# thread_dongle.net
KiCad netlist of a schematic drawn in EAGLE
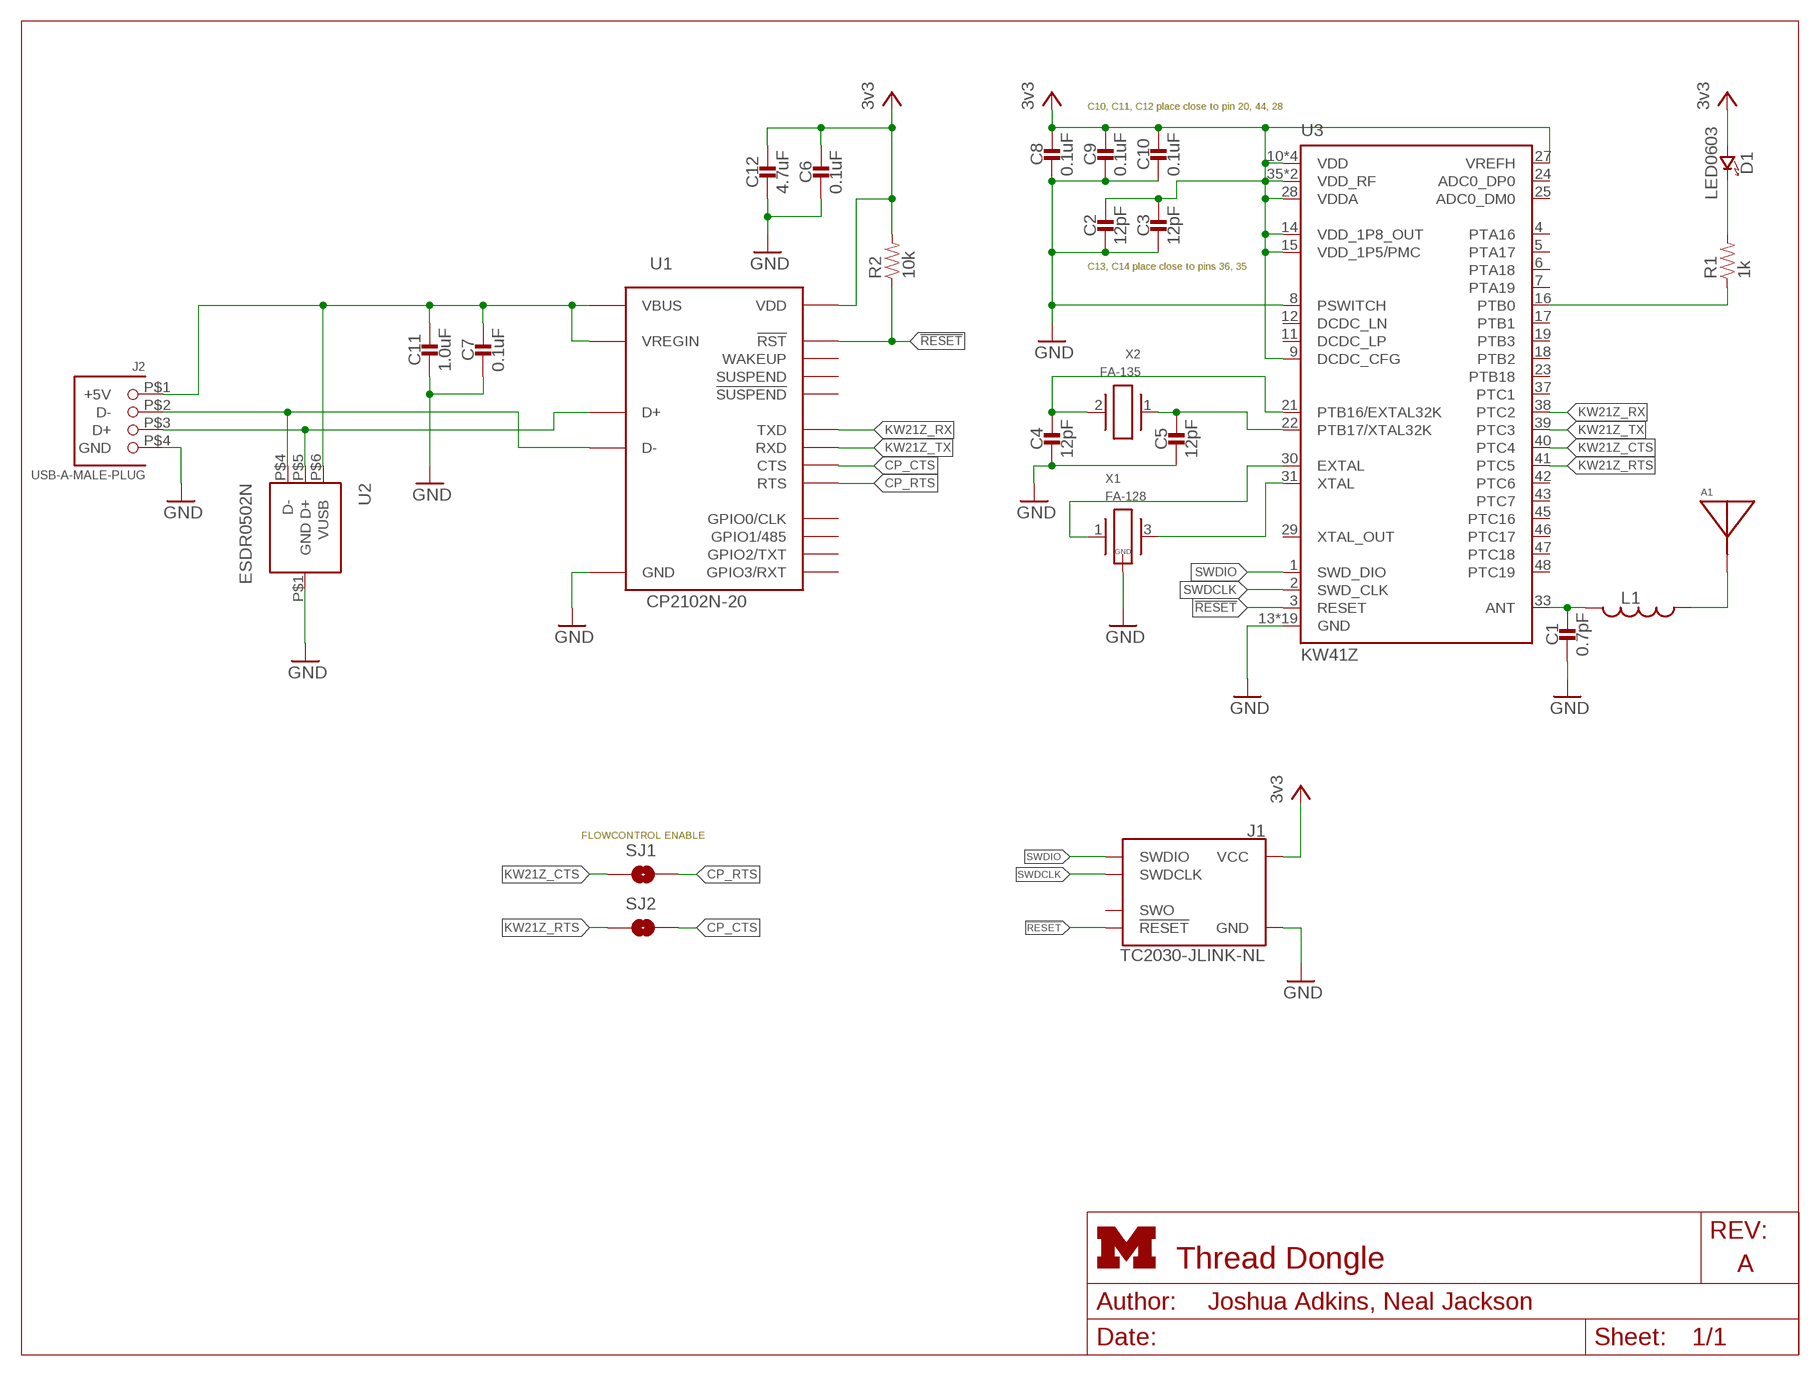
[diagram p0: schematic, sheet 1]

(export (version "E")
  (design (tool "Eeschema 10.0.6"))
  (components
    (comp (ref "A1")
      (value "AH212M")
      (footprint "eagle-import:AH212M")
      (fields (field (name "MPN") "AH212M245001-T"))
      (libsource (lib "eagle-import") (part "AH212M"))
    )
    (comp (ref "C1")
      (value "0.7pF")
      (footprint "eagle-import:0402_CAP")
      (fields (field (name "MPN") "GRM1555C1HR70BA01D"))
      (libsource (lib "eagle-import") (part "CAPACITOR0402_CAP"))
    )
    (comp (ref "C2")
      (value "12pF")
      (footprint "eagle-import:0402_CAP")
      (fields (field (name "MPN") "GRM1555C1H120JA01D"))
      (libsource (lib "eagle-import") (part "CAPACITOR0402_CAP"))
    )
    (comp (ref "C3")
      (value "12pF")
      (footprint "eagle-import:0402_CAP")
      (fields (field (name "MPN") "GRM1555C1H120JA01D"))
      (libsource (lib "eagle-import") (part "CAPACITOR0402_CAP"))
    )
    (comp (ref "C4")
      (value "12pF")
      (footprint "eagle-import:0402_CAP")
      (fields (field (name "MPN") "GRM1555C1H120JA01D"))
      (libsource (lib "eagle-import") (part "CAPACITOR0402_CAP"))
    )
    (comp (ref "C5")
      (value "12pF")
      (footprint "eagle-import:0402_CAP")
      (fields (field (name "MPN") "GRM1555C1H120JA01D"))
      (libsource (lib "eagle-import") (part "CAPACITOR0402_CAP"))
    )
    (comp (ref "C6")
      (value "0.1uF")
      (footprint "eagle-import:0402_CAP")
      (fields (field (name "MPN") "LMK105BJ104KV-F"))
      (libsource (lib "eagle-import") (part "CAPACITOR0402_CAP"))
    )
    (comp (ref "C7")
      (value "0.1uF")
      (footprint "eagle-import:0402_CAP")
      (fields (field (name "MPN") "LMK105BJ104KV-F"))
      (libsource (lib "eagle-import") (part "CAPACITOR0402_CAP"))
    )
    (comp (ref "C8")
      (value "0.1uF")
      (footprint "eagle-import:0402_CAP")
      (fields (field (name "MPN") "LMK105BJ104KV-F"))
      (libsource (lib "eagle-import") (part "CAPACITOR0402_CAP"))
    )
    (comp (ref "C9")
      (value "0.1uF")
      (footprint "eagle-import:0402_CAP")
      (fields (field (name "MPN") "LMK105BJ104KV-F"))
      (libsource (lib "eagle-import") (part "CAPACITOR0402_CAP"))
    )
    (comp (ref "C10")
      (value "0.1uF")
      (footprint "eagle-import:0402_CAP")
      (fields (field (name "MPN") "LMK105BJ104KV-F"))
      (libsource (lib "eagle-import") (part "CAPACITOR0402_CAP"))
    )
    (comp (ref "C11")
      (value "1.0uF")
      (footprint "eagle-import:0402_CAP")
      (fields (field (name "MPN") "GRM155R61E105MA12D"))
      (libsource (lib "eagle-import") (part "CAPACITOR0402_CAP"))
    )
    (comp (ref "C12")
      (value "4.7uF")
      (footprint "eagle-import:0402_CAP")
      (fields (field (name "MPN") "GRM155R60J475ME47D"))
      (libsource (lib "eagle-import") (part "CAPACITOR0402_CAP"))
    )
    (comp (ref "D1")
      (value "LED0603")
      (footprint "eagle-import:LED-0603")
      (fields (field (name "MPN") "LTST-C194TBKT"))
      (libsource (lib "eagle-import") (part "LED0603"))
    )
    (comp (ref "J1")
      (value "TC2030-JLINK-NL")
      (footprint "eagle-import:TC2030-IDC-NL")
      (libsource (lib "eagle-import") (part "TC2030-JLINK-NL"))
    )
    (comp (ref "J2")
      (value "USB-A-MALE-PLUG")
      (footprint "eagle-import:USB_A_MALE_PLUG_CUI_UP2-AH")
      (fields (field (name "MANUFACTURER") "CUI") (field (name "MPN") "UP2-AH-1-TH"))
      (libsource (lib "eagle-import") (part "USB-A-MALE-PLUG"))
    )
    (comp (ref "L1")
      (value "INDUCTOR0402")
      (footprint "eagle-import:0402_CAP")
      (fields (field (name "MPN") "LQG15HS5N1S02D"))
      (libsource (lib "eagle-import") (part "INDUCTOR0402"))
    )
    (comp (ref "R1")
      (value "1k")
      (footprint "eagle-import:0402_RES")
      (fields (field (name "MPN") "RC0402JR-071KL"))
      (libsource (lib "eagle-import") (part "RESISTOR0402_RES"))
    )
    (comp (ref "R2")
      (value "10k")
      (footprint "eagle-import:0402_RES")
      (fields (field (name "MPN") "RC0402JR-0710KL"))
      (libsource (lib "eagle-import") (part "RESISTOR0402_RES"))
    )
    (comp (ref "SJ1")
      (value "SOLDERJUMPERNC")
      (footprint "eagle-import:SJ_2S_SMALL")
      (libsource (lib "eagle-import") (part "SOLDERJUMPERNC"))
    )
    (comp (ref "SJ2")
      (value "SOLDERJUMPERNC")
      (footprint "eagle-import:SJ_2S_SMALL")
      (libsource (lib "eagle-import") (part "SOLDERJUMPERNC"))
    )
    (comp (ref "U1")
      (value "CP2102N-20")
      (footprint "eagle-import:QFN-20-3MM")
      (fields (field (name "MANUFACTURER") "SiLabs") (field (name "MPN") "CP2102N-A01-GQFN20"))
      (libsource (lib "eagle-import") (part "CP2102N-20"))
    )
    (comp (ref "U2")
      (value "ESDR0502N")
      (footprint "eagle-import:UDFN-6")
      (fields (field (name "MPN") "ESDR0502NMUTBG"))
      (libsource (lib "eagle-import") (part "ESDR0502N"))
    )
    (comp (ref "U3")
      (value "KW41Z")
      (footprint "eagle-import:LAMINATE-QFN-48-7MM")
      (fields (field (name "MPN") "MKW41Z512VHT4"))
      (libsource (lib "eagle-import") (part "KW41Z"))
    )
    (comp (ref "X1")
      (value "FA-128")
      (footprint "eagle-import:FA-128")
      (fields (field (name "MPN") "FA-128 32.0000MF20X-K5"))
      (libsource (lib "eagle-import") (part "FA-128"))
    )
    (comp (ref "X2")
      (value "FA-135")
      (footprint "eagle-import:FC-135")
      (fields (field (name "MPN") "FC-135 32.7680KA-AG3"))
      (libsource (lib "eagle-import") (part "FA-135"))
    )
  )
  (nets
    (net (code "1") (name "/~{RESET}") (class "Default")
      (node (ref "J1") (pin "3") (pinfunction "~{RESET}_3") (pintype "bidirectional"))
      (node (ref "R2") (pin "1") (pinfunction "1_1") (pintype "passive"))
      (node (ref "U1") (pin "9") (pinfunction "~{RST}_9") (pintype "bidirectional"))
      (node (ref "U3") (pin "3") (pinfunction "RESET_3") (pintype "bidirectional"))
    )
    (net (code "2") (name "3v3") (class "Default")
      (node (ref "C10") (pin "1") (pinfunction "1_1") (pintype "bidirectional"))
      (node (ref "C12") (pin "1") (pinfunction "1_1") (pintype "bidirectional"))
      (node (ref "C2") (pin "1") (pinfunction "1_1") (pintype "bidirectional"))
      (node (ref "C3") (pin "1") (pinfunction "1_1") (pintype "bidirectional"))
      (node (ref "C6") (pin "1") (pinfunction "1_1") (pintype "bidirectional"))
      (node (ref "C8") (pin "1") (pinfunction "1_1") (pintype "bidirectional"))
      (node (ref "C9") (pin "1") (pinfunction "1_1") (pintype "bidirectional"))
      (node (ref "D1") (pin "A") (pinfunction "ANODE_A") (pintype "bidirectional"))
      (node (ref "J1") (pin "1") (pinfunction "VCC_1") (pintype "bidirectional"))
      (node (ref "R2") (pin "2") (pinfunction "2_2") (pintype "passive"))
      (node (ref "U1") (pin "6") (pinfunction "VDD_6") (pintype "bidirectional"))
      (node (ref "U3") (pin "10") (pinfunction "VDD_10") (pintype "bidirectional"))
      (node (ref "U3") (pin "14") (pinfunction "VDD_1P8_OUT_14") (pintype "bidirectional"))
      (node (ref "U3") (pin "15") (pinfunction "VDD_1P5/PMC_15") (pintype "bidirectional"))
      (node (ref "U3") (pin "20") (pinfunction "VDD_20") (pintype "bidirectional"))
      (node (ref "U3") (pin "27") (pinfunction "VREFH_27") (pintype "bidirectional"))
      (node (ref "U3") (pin "28") (pinfunction "VDDA_28") (pintype "bidirectional"))
      (node (ref "U3") (pin "32") (pinfunction "VDD_32") (pintype "bidirectional"))
      (node (ref "U3") (pin "35") (pinfunction "VDD_RF_35") (pintype "bidirectional"))
      (node (ref "U3") (pin "36") (pinfunction "VDD_RF_36") (pintype "bidirectional"))
      (node (ref "U3") (pin "44") (pinfunction "VDD_44") (pintype "bidirectional"))
      (node (ref "U3") (pin "9") (pinfunction "DCDC_CFG_9") (pintype "bidirectional"))
    )
    (net (code "3") (name "CP_CTS") (class "Default")
      (node (ref "SJ2") (pin "2") (pinfunction "2_2") (pintype "passive"))
      (node (ref "U1") (pin "15") (pinfunction "CTS_15") (pintype "bidirectional"))
    )
    (net (code "4") (name "CP_RTS") (class "Default")
      (node (ref "SJ1") (pin "2") (pinfunction "2_2") (pintype "passive"))
      (node (ref "U1") (pin "16") (pinfunction "RTS_16") (pintype "bidirectional"))
    )
    (net (code "5") (name "GND") (class "Default")
      (node (ref "C1") (pin "2") (pinfunction "2_2") (pintype "bidirectional"))
      (node (ref "C10") (pin "2") (pinfunction "2_2") (pintype "bidirectional"))
      (node (ref "C11") (pin "2") (pinfunction "2_2") (pintype "bidirectional"))
      (node (ref "C12") (pin "2") (pinfunction "2_2") (pintype "bidirectional"))
      (node (ref "C2") (pin "2") (pinfunction "2_2") (pintype "bidirectional"))
      (node (ref "C3") (pin "2") (pinfunction "2_2") (pintype "bidirectional"))
      (node (ref "C4") (pin "2") (pinfunction "2_2") (pintype "bidirectional"))
      (node (ref "C5") (pin "2") (pinfunction "2_2") (pintype "bidirectional"))
      (node (ref "C6") (pin "2") (pinfunction "2_2") (pintype "bidirectional"))
      (node (ref "C7") (pin "2") (pinfunction "2_2") (pintype "bidirectional"))
      (node (ref "C8") (pin "2") (pinfunction "2_2") (pintype "bidirectional"))
      (node (ref "C9") (pin "2") (pinfunction "2_2") (pintype "bidirectional"))
      (node (ref "J1") (pin "5") (pinfunction "GND_5") (pintype "bidirectional"))
      (node (ref "J2") (pin "P$4") (pinfunction "GND_P$4") (pintype "bidirectional"))
      (node (ref "U1") (pin "12") (pinfunction "GND_12") (pintype "bidirectional"))
      (node (ref "U1") (pin "3") (pinfunction "GND_3") (pintype "bidirectional"))
      (node (ref "U1") (pin "P$1") (pinfunction "GND_P$1") (pintype "bidirectional"))
      (node (ref "U2") (pin "P$1") (pinfunction "GND_P$1") (pintype "bidirectional"))
      (node (ref "U3") (pin "13") (pinfunction "GND_13") (pintype "bidirectional"))
      (node (ref "U3") (pin "26") (pinfunction "GND_26") (pintype "bidirectional"))
      (node (ref "U3") (pin "34") (pinfunction "GND_34") (pintype "bidirectional"))
      (node (ref "U3") (pin "49") (pinfunction "GND_49") (pintype "bidirectional"))
      (node (ref "U3") (pin "50") (pinfunction "GND_50") (pintype "bidirectional"))
      (node (ref "U3") (pin "51") (pinfunction "GND_51") (pintype "bidirectional"))
      (node (ref "U3") (pin "52") (pinfunction "GND_52") (pintype "bidirectional"))
      (node (ref "U3") (pin "53") (pinfunction "GND_53") (pintype "bidirectional"))
      (node (ref "U3") (pin "54") (pinfunction "GND_54") (pintype "bidirectional"))
      (node (ref "U3") (pin "55") (pinfunction "GND_55") (pintype "bidirectional"))
      (node (ref "U3") (pin "56") (pinfunction "GND_56") (pintype "bidirectional"))
      (node (ref "U3") (pin "57") (pinfunction "GND_57") (pintype "bidirectional"))
      (node (ref "U3") (pin "58") (pinfunction "GND_58") (pintype "bidirectional"))
      (node (ref "U3") (pin "59") (pinfunction "GND_59") (pintype "bidirectional"))
      (node (ref "U3") (pin "60") (pinfunction "GND_60") (pintype "bidirectional"))
      (node (ref "U3") (pin "61") (pinfunction "GND_61") (pintype "bidirectional"))
      (node (ref "U3") (pin "62") (pinfunction "GND_62") (pintype "bidirectional"))
      (node (ref "U3") (pin "63") (pinfunction "GND_63") (pintype "bidirectional"))
      (node (ref "U3") (pin "64") (pinfunction "GND_64") (pintype "bidirectional"))
      (node (ref "U3") (pin "8") (pinfunction "PSWITCH_8") (pintype "bidirectional"))
      (node (ref "X1") (pin "2") (pinfunction "GND_2") (pintype "bidirectional"))
      (node (ref "X1") (pin "4") (pinfunction "GND_4") (pintype "bidirectional"))
    )
    (net (code "6") (name "KW21Z_CTS") (class "Default")
      (node (ref "SJ1") (pin "1") (pinfunction "1_1") (pintype "passive"))
      (node (ref "U3") (pin "40") (pinfunction "PTC4_40") (pintype "bidirectional"))
    )
    (net (code "7") (name "KW21Z_RTS") (class "Default")
      (node (ref "SJ2") (pin "1") (pinfunction "1_1") (pintype "passive"))
      (node (ref "U3") (pin "41") (pinfunction "PTC5_41") (pintype "bidirectional"))
    )
    (net (code "8") (name "KW21Z_RX") (class "Default")
      (node (ref "U1") (pin "18") (pinfunction "TXD_18") (pintype "bidirectional"))
      (node (ref "U3") (pin "38") (pinfunction "PTC2_38") (pintype "bidirectional"))
    )
    (net (code "9") (name "KW21Z_TX") (class "Default")
      (node (ref "U1") (pin "17") (pinfunction "RXD_17") (pintype "bidirectional"))
      (node (ref "U3") (pin "39") (pinfunction "PTC3_39") (pintype "bidirectional"))
    )
    (net (code "10") (name "Net-(A1-ANTENNA)") (class "Default")
      (node (ref "A1") (pin "P1") (pinfunction "ANTENNA_P1") (pintype "bidirectional"))
      (node (ref "L1") (pin "1") (pinfunction "1_1") (pintype "bidirectional"))
    )
    (net (code "11") (name "Net-(D1-CATHODE)") (class "Default")
      (node (ref "D1") (pin "C") (pinfunction "CATHODE_C") (pintype "bidirectional"))
      (node (ref "R1") (pin "2") (pinfunction "2_2") (pintype "passive"))
    )
    (net (code "12") (name "Net-(J2-+5V)") (class "Default")
      (node (ref "C11") (pin "1") (pinfunction "1_1") (pintype "bidirectional"))
      (node (ref "C7") (pin "1") (pinfunction "1_1") (pintype "bidirectional"))
      (node (ref "J2") (pin "P$1") (pinfunction "+5V_P$1") (pintype "bidirectional"))
      (node (ref "U1") (pin "7") (pinfunction "VREGIN_7") (pintype "bidirectional"))
      (node (ref "U1") (pin "8") (pinfunction "VBUS_8") (pintype "bidirectional"))
      (node (ref "U2") (pin "P$6") (pinfunction "VUSB_P$6") (pintype "bidirectional"))
    )
    (net (code "13") (name "Net-(J2-D+)") (class "Default")
      (node (ref "J2") (pin "P$3") (pinfunction "D+_P$3") (pintype "bidirectional"))
      (node (ref "U1") (pin "4") (pinfunction "D+_4") (pintype "bidirectional"))
      (node (ref "U2") (pin "P$5") (pinfunction "D+_P$5") (pintype "bidirectional"))
    )
    (net (code "14") (name "Net-(J2-D-)") (class "Default")
      (node (ref "J2") (pin "P$2") (pinfunction "D-_P$2") (pintype "bidirectional"))
      (node (ref "U1") (pin "5") (pinfunction "D-_5") (pintype "bidirectional"))
      (node (ref "U2") (pin "P$4") (pinfunction "D-_P$4") (pintype "bidirectional"))
    )
    (net (code "15") (name "Net-(U3-ANT)") (class "Default")
      (node (ref "C1") (pin "1") (pinfunction "1_1") (pintype "bidirectional"))
      (node (ref "L1") (pin "2") (pinfunction "2_2") (pintype "bidirectional"))
      (node (ref "U3") (pin "33") (pinfunction "ANT_33") (pintype "bidirectional"))
    )
    (net (code "16") (name "Net-(U3-EXTAL)") (class "Default")
      (node (ref "U3") (pin "30") (pinfunction "EXTAL_30") (pintype "bidirectional"))
      (node (ref "X1") (pin "1") (pinfunction "1_1") (pintype "bidirectional"))
    )
    (net (code "17") (name "Net-(U3-PTB0)") (class "Default")
      (node (ref "R1") (pin "1") (pinfunction "1_1") (pintype "passive"))
      (node (ref "U3") (pin "16") (pinfunction "PTB0_16") (pintype "bidirectional"))
    )
    (net (code "18") (name "Net-(U3-PTB16{slash}EXTAL32K)") (class "Default")
      (node (ref "C4") (pin "1") (pinfunction "1_1") (pintype "bidirectional"))
      (node (ref "U3") (pin "21") (pinfunction "PTB16/EXTAL32K_21") (pintype "bidirectional"))
      (node (ref "X2") (pin "2") (pinfunction "2_2") (pintype "bidirectional"))
    )
    (net (code "19") (name "Net-(U3-PTB17{slash}XTAL32K)") (class "Default")
      (node (ref "C5") (pin "1") (pinfunction "1_1") (pintype "bidirectional"))
      (node (ref "U3") (pin "22") (pinfunction "PTB17/XTAL32K_22") (pintype "bidirectional"))
      (node (ref "X2") (pin "1") (pinfunction "1_1") (pintype "bidirectional"))
    )
    (net (code "20") (name "Net-(U3-XTAL)") (class "Default")
      (node (ref "U3") (pin "31") (pinfunction "XTAL_31") (pintype "bidirectional"))
      (node (ref "X1") (pin "3") (pinfunction "2_3") (pintype "bidirectional"))
    )
    (net (code "21") (name "SWDCLK") (class "Default")
      (node (ref "J1") (pin "4") (pinfunction "SWDCLK_4") (pintype "bidirectional"))
      (node (ref "U3") (pin "2") (pinfunction "SWD_CLK_2") (pintype "bidirectional"))
    )
    (net (code "22") (name "SWDIO") (class "Default")
      (node (ref "J1") (pin "2") (pinfunction "SWDIO_2") (pintype "bidirectional"))
      (node (ref "U3") (pin "1") (pinfunction "SWD_DIO_1") (pintype "bidirectional"))
    )
    (net (code "23") (name "unconnected-(J1-SWO-Pad6)") (class "Default")
      (node (ref "J1") (pin "6") (pinfunction "SWO_6") (pintype "bidirectional"))
    )
    (net (code "24") (name "unconnected-(U1-GPIO0{slash}CLK-Pad2)") (class "Default")
      (node (ref "U1") (pin "2") (pinfunction "GPIO0/CLK_2") (pintype "bidirectional"))
    )
    (net (code "25") (name "unconnected-(U1-GPIO1{slash}485-Pad1)") (class "Default")
      (node (ref "U1") (pin "1") (pinfunction "GPIO1/485_1") (pintype "bidirectional"))
    )
    (net (code "26") (name "unconnected-(U1-GPIO2{slash}TXT-Pad20)") (class "Default")
      (node (ref "U1") (pin "20") (pinfunction "GPIO2/TXT_20") (pintype "bidirectional"))
    )
    (net (code "27") (name "unconnected-(U1-GPIO3{slash}RXT-Pad19)") (class "Default")
      (node (ref "U1") (pin "19") (pinfunction "GPIO3/RXT_19") (pintype "bidirectional"))
    )
    (net (code "28") (name "unconnected-(U1-SUSPEND-Pad14)") (class "Default")
      (node (ref "U1") (pin "14") (pinfunction "SUSPEND_14") (pintype "bidirectional"))
    )
    (net (code "29") (name "unconnected-(U1-WAKEUP-Pad13)") (class "Default")
      (node (ref "U1") (pin "13") (pinfunction "WAKEUP_13") (pintype "bidirectional"))
    )
    (net (code "30") (name "unconnected-(U1-~{SUSPEND}-Pad11)") (class "Default")
      (node (ref "U1") (pin "11") (pinfunction "~{SUSPEND}_11") (pintype "bidirectional"))
    )
    (net (code "31") (name "unconnected-(U3-ADC0_DM0-Pad25)") (class "Default")
      (node (ref "U3") (pin "25") (pinfunction "ADC0_DM0_25") (pintype "bidirectional"))
    )
    (net (code "32") (name "unconnected-(U3-ADC0_DP0-Pad24)") (class "Default")
      (node (ref "U3") (pin "24") (pinfunction "ADC0_DP0_24") (pintype "bidirectional"))
    )
    (net (code "33") (name "unconnected-(U3-DCDC_LN-Pad12)") (class "Default")
      (node (ref "U3") (pin "12") (pinfunction "DCDC_LN_12") (pintype "bidirectional"))
    )
    (net (code "34") (name "unconnected-(U3-DCDC_LP-Pad11)") (class "Default")
      (node (ref "U3") (pin "11") (pinfunction "DCDC_LP_11") (pintype "bidirectional"))
    )
    (net (code "35") (name "unconnected-(U3-PTA16-Pad4)") (class "Default")
      (node (ref "U3") (pin "4") (pinfunction "PTA16_4") (pintype "bidirectional"))
    )
    (net (code "36") (name "unconnected-(U3-PTA17-Pad5)") (class "Default")
      (node (ref "U3") (pin "5") (pinfunction "PTA17_5") (pintype "bidirectional"))
    )
    (net (code "37") (name "unconnected-(U3-PTA18-Pad6)") (class "Default")
      (node (ref "U3") (pin "6") (pinfunction "PTA18_6") (pintype "bidirectional"))
    )
    (net (code "38") (name "unconnected-(U3-PTA19-Pad7)") (class "Default")
      (node (ref "U3") (pin "7") (pinfunction "PTA19_7") (pintype "bidirectional"))
    )
    (net (code "39") (name "unconnected-(U3-PTB1-Pad17)") (class "Default")
      (node (ref "U3") (pin "17") (pinfunction "PTB1_17") (pintype "bidirectional"))
    )
    (net (code "40") (name "unconnected-(U3-PTB2-Pad18)") (class "Default")
      (node (ref "U3") (pin "18") (pinfunction "PTB2_18") (pintype "bidirectional"))
    )
    (net (code "41") (name "unconnected-(U3-PTB3-Pad19)") (class "Default")
      (node (ref "U3") (pin "19") (pinfunction "PTB3_19") (pintype "bidirectional"))
    )
    (net (code "42") (name "unconnected-(U3-PTB18-Pad23)") (class "Default")
      (node (ref "U3") (pin "23") (pinfunction "PTB18_23") (pintype "bidirectional"))
    )
    (net (code "43") (name "unconnected-(U3-PTC1-Pad37)") (class "Default")
      (node (ref "U3") (pin "37") (pinfunction "PTC1_37") (pintype "bidirectional"))
    )
    (net (code "44") (name "unconnected-(U3-PTC6-Pad42)") (class "Default")
      (node (ref "U3") (pin "42") (pinfunction "PTC6_42") (pintype "bidirectional"))
    )
    (net (code "45") (name "unconnected-(U3-PTC7-Pad43)") (class "Default")
      (node (ref "U3") (pin "43") (pinfunction "PTC7_43") (pintype "bidirectional"))
    )
    (net (code "46") (name "unconnected-(U3-PTC16-Pad45)") (class "Default")
      (node (ref "U3") (pin "45") (pinfunction "PTC16_45") (pintype "bidirectional"))
    )
    (net (code "47") (name "unconnected-(U3-PTC17-Pad46)") (class "Default")
      (node (ref "U3") (pin "46") (pinfunction "PTC17_46") (pintype "bidirectional"))
    )
    (net (code "48") (name "unconnected-(U3-PTC18-Pad47)") (class "Default")
      (node (ref "U3") (pin "47") (pinfunction "PTC18_47") (pintype "bidirectional"))
    )
    (net (code "49") (name "unconnected-(U3-PTC19-Pad48)") (class "Default")
      (node (ref "U3") (pin "48") (pinfunction "PTC19_48") (pintype "bidirectional"))
    )
    (net (code "50") (name "unconnected-(U3-XTAL_OUT-Pad29)") (class "Default")
      (node (ref "U3") (pin "29") (pinfunction "XTAL_OUT_29") (pintype "bidirectional"))
    )
  )
)
